# MainBoard_project.net
KiCad netlist of a schematic drawn in EAGLE
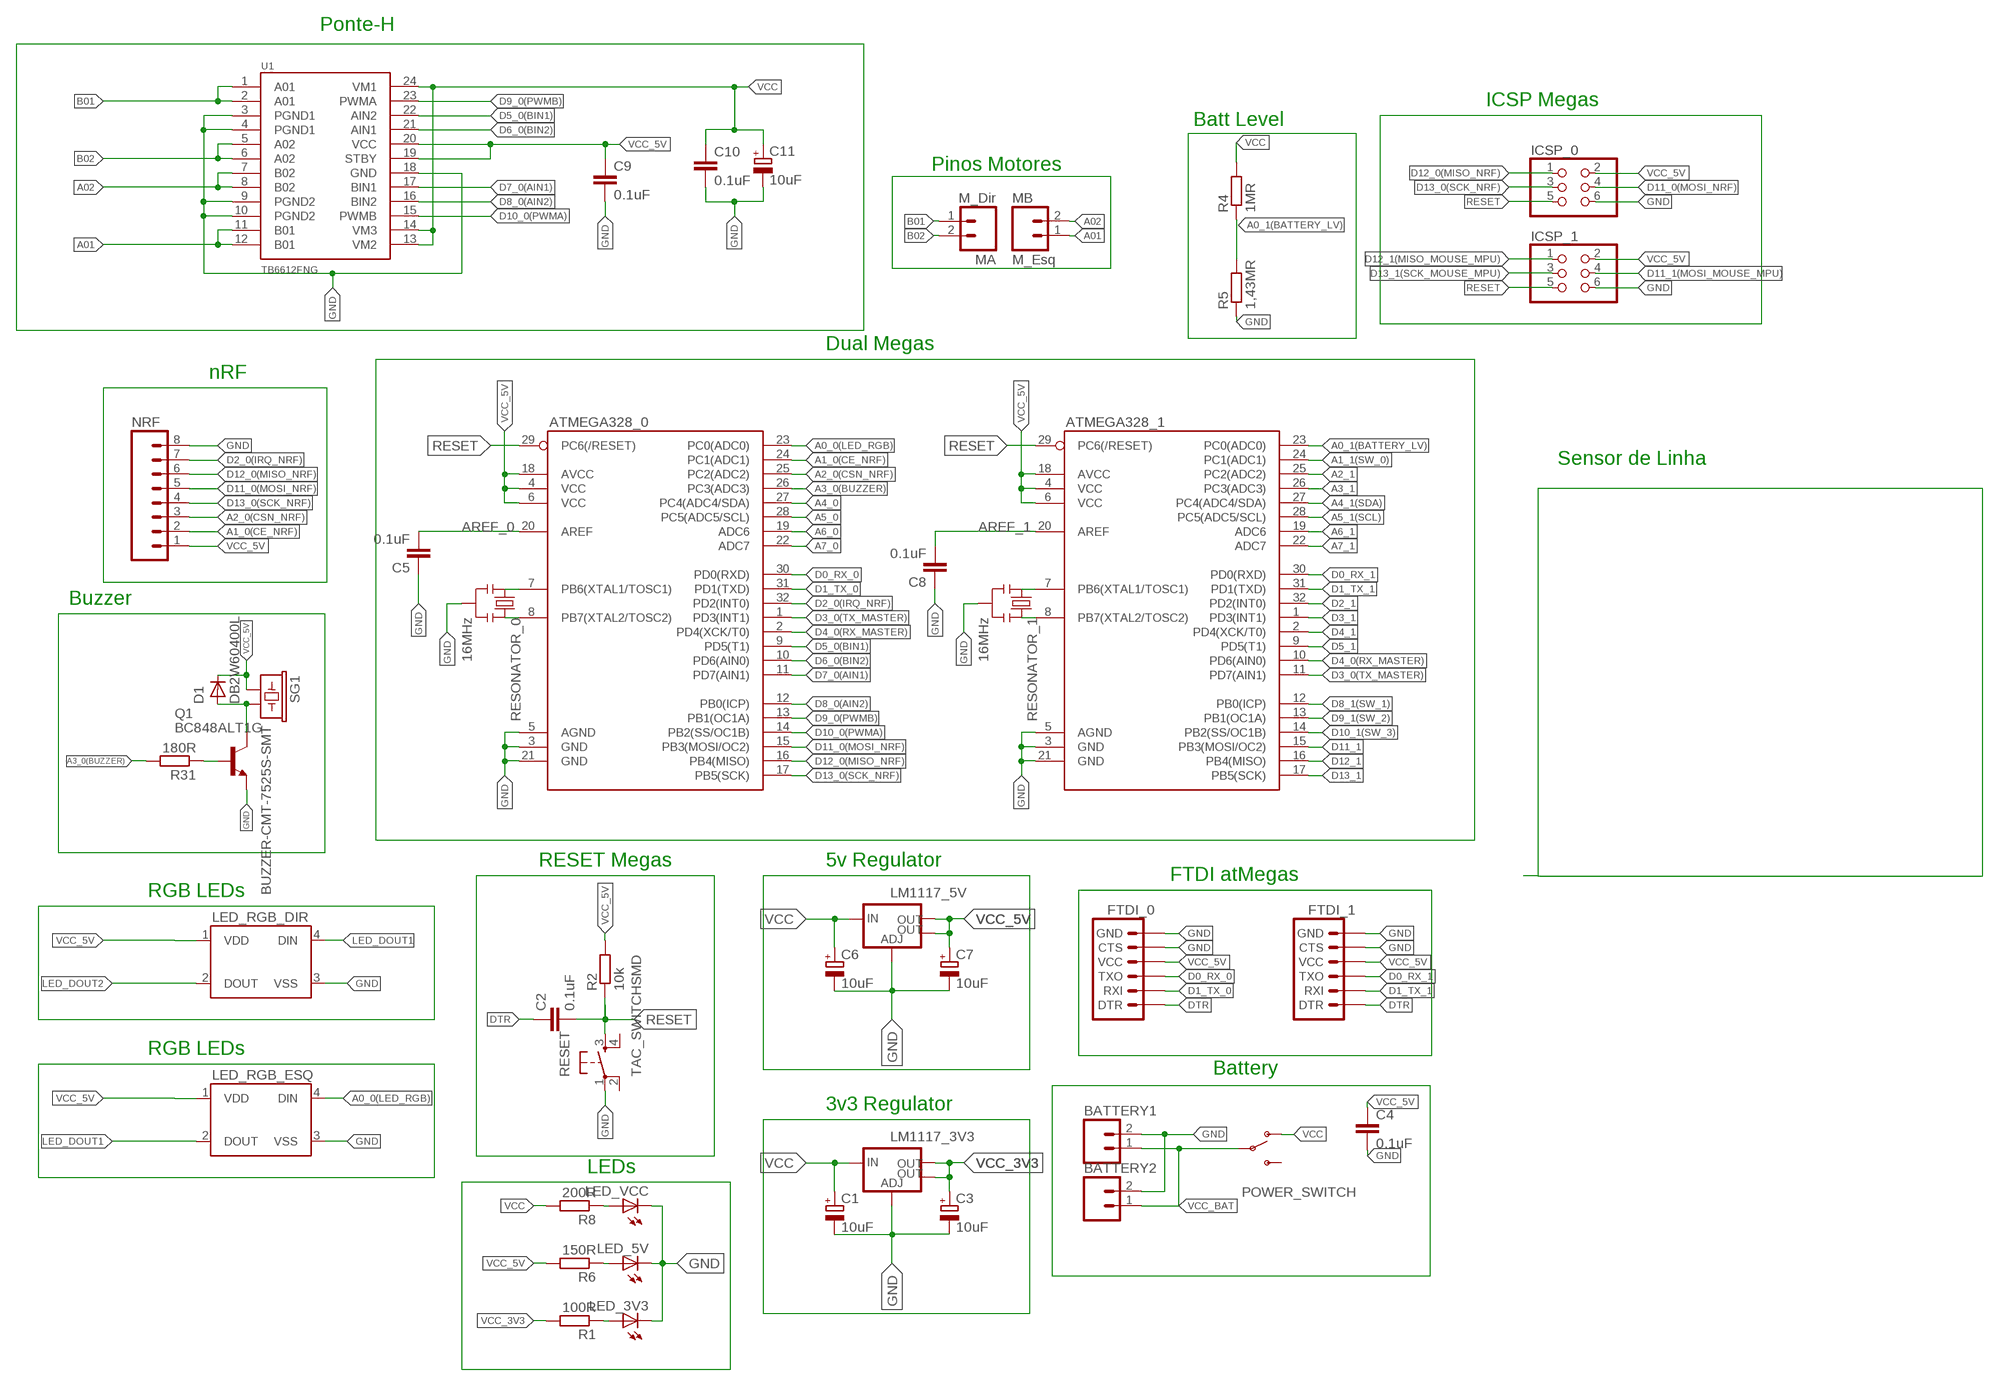
[diagram p0: schematic, sheet 1]

(export (version "E")
  (design (tool "Eeschema 10.0.6"))
  (components
    (comp (ref "ATMEGA328_0")
      (value "ATMEGA168")
      (footprint "eagle-import:TQFP32-08")
      (libsource (lib "eagle-import") (part "ATMEGA168"))
    )
    (comp (ref "ATMEGA328_1")
      (value "ATMEGA168")
      (footprint "eagle-import:TQFP32-08")
      (libsource (lib "eagle-import") (part "ATMEGA168"))
    )
    (comp (ref "BATTERY1")
      (value "M02POLAR")
      (footprint "eagle-import:MOLEX-1X2")
      (libsource (lib "eagle-import") (part "M02POLAR"))
    )
    (comp (ref "BATTERY2")
      (value "M02POLAR")
      (footprint "eagle-import:MOLEX-1X2")
      (libsource (lib "eagle-import") (part "M02POLAR"))
    )
    (comp (ref "C1")
      (value "10uF")
      (footprint "eagle-import:B_3528-21W")
      (libsource (lib "eagle-import") (part "CPOL-EUB/3528-21W"))
    )
    (comp (ref "C2")
      (value "0.1uF")
      (footprint "eagle-import:C0805K")
      (libsource (lib "eagle-import") (part "C-EUC0805K"))
    )
    (comp (ref "C3")
      (value "10uF")
      (footprint "eagle-import:B_3528-21W")
      (libsource (lib "eagle-import") (part "CPOL-EUB/3528-21W"))
    )
    (comp (ref "C4")
      (value "0.1uF")
      (footprint "eagle-import:C0805K")
      (libsource (lib "eagle-import") (part "C-EUC0805K"))
    )
    (comp (ref "C5")
      (value "0.1uF")
      (footprint "eagle-import:C0805K")
      (libsource (lib "eagle-import") (part "C-EUC0805K"))
    )
    (comp (ref "C6")
      (value "10uF")
      (footprint "eagle-import:B_3528-21W")
      (libsource (lib "eagle-import") (part "CPOL-EUB/3528-21W"))
    )
    (comp (ref "C7")
      (value "10uF")
      (footprint "eagle-import:B_3528-21W")
      (libsource (lib "eagle-import") (part "CPOL-EUB/3528-21W"))
    )
    (comp (ref "C8")
      (value "0.1uF")
      (footprint "eagle-import:C0805K")
      (libsource (lib "eagle-import") (part "C-EUC0805K"))
    )
    (comp (ref "C9")
      (value "0.1uF")
      (footprint "eagle-import:C0805K")
      (libsource (lib "eagle-import") (part "C-EUC0805K"))
    )
    (comp (ref "C10")
      (value "0.1uF")
      (footprint "eagle-import:C0805K")
      (libsource (lib "eagle-import") (part "C-EUC0805K"))
    )
    (comp (ref "C11")
      (value "10uF")
      (footprint "eagle-import:B_3528-21W")
      (libsource (lib "eagle-import") (part "CPOL-EUB/3528-21W"))
    )
    (comp (ref "D1")
      (value "DB2W60400L")
      (footprint "eagle-import:SMA-DO214AC")
      (libsource (lib "eagle-import") (part "GF1"))
    )
    (comp (ref "FTDI_0")
      (value "ARDUINO_SERIAL_PROGRAMPTH")
      (footprint "eagle-import:1X06")
      (libsource (lib "eagle-import") (part "ARDUINO_SERIAL_PROGRAMPTH"))
    )
    (comp (ref "FTDI_1")
      (value "ARDUINO_SERIAL_PROGRAMPTH")
      (footprint "eagle-import:1X06")
      (libsource (lib "eagle-import") (part "ARDUINO_SERIAL_PROGRAMPTH"))
    )
    (comp (ref "ICSP_0")
      (value "0114_PH254-203DF118A00V")
      (footprint "eagle-import:2X03")
      (fields (field (name "PART_NUMBER") "PH254-203DF118A00V"))
      (libsource (lib "eagle-import") (part "0114_PH254-203DF118A00V"))
    )
    (comp (ref "ICSP_1")
      (value "0114_PH254-203DF118A00V")
      (footprint "eagle-import:2X03")
      (fields (field (name "PART_NUMBER") "PH254-203DF118A00V"))
      (libsource (lib "eagle-import") (part "0114_PH254-203DF118A00V"))
    )
    (comp (ref "LED_3V3")
      (value "LEDCHIP-LED0805")
      (footprint "eagle-import:CHIP-LED0805")
      (libsource (lib "eagle-import") (part "LEDCHIP-LED0805"))
    )
    (comp (ref "LED_5V")
      (value "LEDCHIP-LED0805")
      (footprint "eagle-import:CHIP-LED0805")
      (libsource (lib "eagle-import") (part "LEDCHIP-LED0805"))
    )
    (comp (ref "LED_RGB_DIR")
      (value "WS2812B")
      (footprint "eagle-import:WS2812B")
      (libsource (lib "eagle-import") (part "WS2812B"))
    )
    (comp (ref "LED_RGB_ESQ")
      (value "WS2812B")
      (footprint "eagle-import:WS2812B")
      (libsource (lib "eagle-import") (part "WS2812B"))
    )
    (comp (ref "LED_VCC")
      (value "LEDCHIP-LED0805")
      (footprint "eagle-import:CHIP-LED0805")
      (libsource (lib "eagle-import") (part "LEDCHIP-LED0805"))
    )
    (comp (ref "LM1117_3V3")
      (value "V_REG_LM1117SOT223")
      (footprint "eagle-import:SOT223")
      (libsource (lib "eagle-import") (part "V_REG_LM1117SOT223"))
    )
    (comp (ref "LM1117_5V")
      (value "V_REG_LM1117SOT223")
      (footprint "eagle-import:SOT223")
      (libsource (lib "eagle-import") (part "V_REG_LM1117SOT223"))
    )
    (comp (ref "MA")
      (value "M_Dir")
      (footprint "eagle-import:MOLEX-1X2")
      (libsource (lib "eagle-import") (part "M02POLAR"))
    )
    (comp (ref "MB")
      (value "M_Esq")
      (footprint "eagle-import:MOLEX-1X2")
      (libsource (lib "eagle-import") (part "M02POLAR"))
    )
    (comp (ref "NRF")
      (value "M08")
      (footprint "eagle-import:1X08_ROUND")
      (libsource (lib "eagle-import") (part "M08"))
    )
    (comp (ref "POWER_SWITCH")
      (value "SWITCH-SPDTPTH")
      (footprint "eagle-import:SWITCH-SPDT")
      (libsource (lib "eagle-import") (part "SWITCH-SPDTPTH"))
    )
    (comp (ref "Q1")
      (value "BC848ALT1G")
      (footprint "eagle-import:SOT23")
      (libsource (lib "eagle-import") (part "BC848SMDALT1"))
    )
    (comp (ref "R1")
      (value "100R")
      (footprint "eagle-import:R0805")
      (libsource (lib "eagle-import") (part "R-EU_R0805"))
    )
    (comp (ref "R2")
      (value "10k")
      (footprint "eagle-import:R0805")
      (libsource (lib "eagle-import") (part "R-EU_R0805"))
    )
    (comp (ref "R4")
      (value "1MR")
      (footprint "eagle-import:R0805")
      (libsource (lib "eagle-import") (part "R-EU_R0805"))
    )
    (comp (ref "R5")
      (value "1,43MR")
      (footprint "eagle-import:R0805")
      (libsource (lib "eagle-import") (part "R-EU_R0805"))
    )
    (comp (ref "R6")
      (value "150R")
      (footprint "eagle-import:R0805")
      (libsource (lib "eagle-import") (part "R-EU_R0805"))
    )
    (comp (ref "R8")
      (value "200R")
      (footprint "eagle-import:R0805")
      (libsource (lib "eagle-import") (part "R-EU_R0805"))
    )
    (comp (ref "R31")
      (value "180R")
      (footprint "eagle-import:R0805")
      (libsource (lib "eagle-import") (part "R-EU_R0805"))
    )
    (comp (ref "RESET")
      (value "TAC_SWITCHSMD")
      (footprint "eagle-import:TACTILE-SWITCH-SMD")
      (libsource (lib "eagle-import") (part "TAC_SWITCHSMD"))
    )
    (comp (ref "RESONATOR_0")
      (value "16MHz")
      (footprint "eagle-import:RESONATOR-SMD")
      (libsource (lib "eagle-import") (part "RESONATOR16MHZ"))
    )
    (comp (ref "RESONATOR_1")
      (value "16MHz")
      (footprint "eagle-import:RESONATOR-SMD")
      (libsource (lib "eagle-import") (part "RESONATOR16MHZ"))
    )
    (comp (ref "SG1")
      (value "BUZZER-CMT-7525S-SMT")
      (footprint "eagle-import:CMT-7525S-SMT")
      (libsource (lib "eagle-import") (part "BUZZER-CMT-7525S-SMT"))
    )
    (comp (ref "U1")
      (value "TB6612FNG")
      (footprint "eagle-import:SSOP24")
      (libsource (lib "eagle-import") (part "TB6621FNG"))
    )
  )
  (nets
    (net (code "1") (name "/AREF_0") (class "Default")
      (node (ref "ATMEGA328_0") (pin "20") (pinfunction "AREF_20") (pintype "bidirectional"))
      (node (ref "C5") (pin "2") (pinfunction "2_2") (pintype "passive"))
    )
    (net (code "2") (name "/AREF_1") (class "Default")
      (node (ref "ATMEGA328_1") (pin "20") (pinfunction "AREF_20") (pintype "bidirectional"))
      (node (ref "C8") (pin "2") (pinfunction "2_2") (pintype "passive"))
    )
    (net (code "3") (name "A0_0(LED_RGB)") (class "Default")
      (node (ref "ATMEGA328_0") (pin "23") (pinfunction "PC0(ADC0)_23") (pintype "bidirectional"))
      (node (ref "LED_RGB_ESQ") (pin "4") (pinfunction "DIN_4") (pintype "input"))
    )
    (net (code "4") (name "A0_1(BATTERY_LV)") (class "Default")
      (node (ref "ATMEGA328_1") (pin "23") (pinfunction "PC0(ADC0)_23") (pintype "bidirectional"))
      (node (ref "R4") (pin "1") (pinfunction "1_1") (pintype "passive"))
      (node (ref "R5") (pin "2") (pinfunction "2_2") (pintype "passive"))
    )
    (net (code "5") (name "A01") (class "Default")
      (node (ref "MB") (pin "1") (pinfunction "1_1") (pintype "passive"))
      (node (ref "U1") (pin "11") (pinfunction "B01_11") (pintype "bidirectional"))
      (node (ref "U1") (pin "12") (pinfunction "B01_12") (pintype "bidirectional"))
    )
    (net (code "6") (name "A1_0(CE_NRF)") (class "Default")
      (node (ref "ATMEGA328_0") (pin "24") (pinfunction "PC1(ADC1)_24") (pintype "bidirectional"))
      (node (ref "NRF") (pin "2") (pinfunction "2_2") (pintype "passive"))
    )
    (net (code "7") (name "A1_1(SW_0)") (class "Default")
      (node (ref "ATMEGA328_1") (pin "24") (pinfunction "PC1(ADC1)_24") (pintype "bidirectional"))
    )
    (net (code "8") (name "A02") (class "Default")
      (node (ref "MB") (pin "2") (pinfunction "2_2") (pintype "passive"))
      (node (ref "U1") (pin "7") (pinfunction "B02_7") (pintype "bidirectional"))
      (node (ref "U1") (pin "8") (pinfunction "B02_8") (pintype "bidirectional"))
    )
    (net (code "9") (name "A2_0(CSN_NRF)") (class "Default")
      (node (ref "ATMEGA328_0") (pin "25") (pinfunction "PC2(ADC2)_25") (pintype "bidirectional"))
      (node (ref "NRF") (pin "3") (pinfunction "3_3") (pintype "passive"))
    )
    (net (code "10") (name "A2_1") (class "Default")
      (node (ref "ATMEGA328_1") (pin "25") (pinfunction "PC2(ADC2)_25") (pintype "bidirectional"))
    )
    (net (code "11") (name "A3_0(BUZZER)") (class "Default")
      (node (ref "ATMEGA328_0") (pin "26") (pinfunction "PC3(ADC3)_26") (pintype "bidirectional"))
      (node (ref "R31") (pin "2") (pinfunction "2_2") (pintype "passive"))
    )
    (net (code "12") (name "A3_1") (class "Default")
      (node (ref "ATMEGA328_1") (pin "26") (pinfunction "PC3(ADC3)_26") (pintype "bidirectional"))
    )
    (net (code "13") (name "A4_0") (class "Default")
      (node (ref "ATMEGA328_0") (pin "27") (pinfunction "PC4(ADC4/SDA)_27") (pintype "bidirectional"))
    )
    (net (code "14") (name "A4_1(SDA)") (class "Default")
      (node (ref "ATMEGA328_1") (pin "27") (pinfunction "PC4(ADC4/SDA)_27") (pintype "bidirectional"))
    )
    (net (code "15") (name "A5_0") (class "Default")
      (node (ref "ATMEGA328_0") (pin "28") (pinfunction "PC5(ADC5/SCL)_28") (pintype "bidirectional"))
    )
    (net (code "16") (name "A5_1(SCL)") (class "Default")
      (node (ref "ATMEGA328_1") (pin "28") (pinfunction "PC5(ADC5/SCL)_28") (pintype "bidirectional"))
    )
    (net (code "17") (name "A6_0") (class "Default")
      (node (ref "ATMEGA328_0") (pin "19") (pinfunction "ADC6_19") (pintype "bidirectional"))
    )
    (net (code "18") (name "A6_1") (class "Default")
      (node (ref "ATMEGA328_1") (pin "19") (pinfunction "ADC6_19") (pintype "bidirectional"))
    )
    (net (code "19") (name "A7_0") (class "Default")
      (node (ref "ATMEGA328_0") (pin "22") (pinfunction "ADC7_22") (pintype "bidirectional"))
    )
    (net (code "20") (name "A7_1") (class "Default")
      (node (ref "ATMEGA328_1") (pin "22") (pinfunction "ADC7_22") (pintype "bidirectional"))
    )
    (net (code "21") (name "B01") (class "Default")
      (node (ref "MA") (pin "1") (pinfunction "1_1") (pintype "passive"))
      (node (ref "U1") (pin "1") (pinfunction "A01_1") (pintype "bidirectional"))
      (node (ref "U1") (pin "2") (pinfunction "A01_2") (pintype "bidirectional"))
    )
    (net (code "22") (name "B02") (class "Default")
      (node (ref "MA") (pin "2") (pinfunction "2_2") (pintype "passive"))
      (node (ref "U1") (pin "5") (pinfunction "A02_5") (pintype "bidirectional"))
      (node (ref "U1") (pin "6") (pinfunction "A02_6") (pintype "bidirectional"))
    )
    (net (code "23") (name "D0_RX_0") (class "Default")
      (node (ref "ATMEGA328_0") (pin "30") (pinfunction "PD0(RXD)_30") (pintype "bidirectional"))
      (node (ref "FTDI_0") (pin "3") (pinfunction "TXO_3") (pintype "passive"))
    )
    (net (code "24") (name "D0_RX_1") (class "Default")
      (node (ref "ATMEGA328_1") (pin "30") (pinfunction "PD0(RXD)_30") (pintype "bidirectional"))
      (node (ref "FTDI_1") (pin "3") (pinfunction "TXO_3") (pintype "passive"))
    )
    (net (code "25") (name "D1_TX_0") (class "Default")
      (node (ref "ATMEGA328_0") (pin "31") (pinfunction "PD1(TXD)_31") (pintype "bidirectional"))
      (node (ref "FTDI_0") (pin "2") (pinfunction "RXI_2") (pintype "passive"))
    )
    (net (code "26") (name "D1_TX_1") (class "Default")
      (node (ref "ATMEGA328_1") (pin "31") (pinfunction "PD1(TXD)_31") (pintype "bidirectional"))
      (node (ref "FTDI_1") (pin "2") (pinfunction "RXI_2") (pintype "passive"))
    )
    (net (code "27") (name "D2_0(IRQ_NRF)") (class "Default")
      (node (ref "ATMEGA328_0") (pin "32") (pinfunction "PD2(INT0)_32") (pintype "bidirectional"))
      (node (ref "NRF") (pin "7") (pinfunction "7_7") (pintype "passive"))
    )
    (net (code "28") (name "D2_1") (class "Default")
      (node (ref "ATMEGA328_1") (pin "32") (pinfunction "PD2(INT0)_32") (pintype "bidirectional"))
    )
    (net (code "29") (name "D3_0(TX_MASTER)") (class "Default")
      (node (ref "ATMEGA328_0") (pin "1") (pinfunction "PD3(INT1)_1") (pintype "bidirectional"))
      (node (ref "ATMEGA328_1") (pin "11") (pinfunction "PD7(AIN1)_11") (pintype "bidirectional"))
    )
    (net (code "30") (name "D3_1") (class "Default")
      (node (ref "ATMEGA328_1") (pin "1") (pinfunction "PD3(INT1)_1") (pintype "bidirectional"))
    )
    (net (code "31") (name "D4_0(RX_MASTER)") (class "Default")
      (node (ref "ATMEGA328_0") (pin "2") (pinfunction "PD4(XCK/T0)_2") (pintype "bidirectional"))
      (node (ref "ATMEGA328_1") (pin "10") (pinfunction "PD6(AIN0)_10") (pintype "bidirectional"))
    )
    (net (code "32") (name "D4_1") (class "Default")
      (node (ref "ATMEGA328_1") (pin "2") (pinfunction "PD4(XCK/T0)_2") (pintype "bidirectional"))
    )
    (net (code "33") (name "D5_0(BIN1)") (class "Default")
      (node (ref "ATMEGA328_0") (pin "9") (pinfunction "PD5(T1)_9") (pintype "bidirectional"))
      (node (ref "U1") (pin "22") (pinfunction "AIN2_22") (pintype "bidirectional"))
    )
    (net (code "34") (name "D5_1") (class "Default")
      (node (ref "ATMEGA328_1") (pin "9") (pinfunction "PD5(T1)_9") (pintype "bidirectional"))
    )
    (net (code "35") (name "D6_0(BIN2)") (class "Default")
      (node (ref "ATMEGA328_0") (pin "10") (pinfunction "PD6(AIN0)_10") (pintype "bidirectional"))
      (node (ref "U1") (pin "21") (pinfunction "AIN1_21") (pintype "bidirectional"))
    )
    (net (code "36") (name "D7_0(AIN1)") (class "Default")
      (node (ref "ATMEGA328_0") (pin "11") (pinfunction "PD7(AIN1)_11") (pintype "bidirectional"))
      (node (ref "U1") (pin "17") (pinfunction "BIN1_17") (pintype "bidirectional"))
    )
    (net (code "37") (name "D8_0(AIN2)") (class "Default")
      (node (ref "ATMEGA328_0") (pin "12") (pinfunction "PB0(ICP)_12") (pintype "bidirectional"))
      (node (ref "U1") (pin "16") (pinfunction "BIN2_16") (pintype "bidirectional"))
    )
    (net (code "38") (name "D8_1(SW_1)") (class "Default")
      (node (ref "ATMEGA328_1") (pin "12") (pinfunction "PB0(ICP)_12") (pintype "bidirectional"))
    )
    (net (code "39") (name "D9_0(PWMB)") (class "Default")
      (node (ref "ATMEGA328_0") (pin "13") (pinfunction "PB1(OC1A)_13") (pintype "bidirectional"))
      (node (ref "U1") (pin "23") (pinfunction "PWMA_23") (pintype "bidirectional"))
    )
    (net (code "40") (name "D9_1(SW_2)") (class "Default")
      (node (ref "ATMEGA328_1") (pin "13") (pinfunction "PB1(OC1A)_13") (pintype "bidirectional"))
    )
    (net (code "41") (name "D10_0(PWMA)") (class "Default")
      (node (ref "ATMEGA328_0") (pin "14") (pinfunction "PB2(SS/OC1B)_14") (pintype "bidirectional"))
      (node (ref "U1") (pin "15") (pinfunction "PWMB_15") (pintype "bidirectional"))
    )
    (net (code "42") (name "D10_1(SW_3)") (class "Default")
      (node (ref "ATMEGA328_1") (pin "14") (pinfunction "PB2(SS/OC1B)_14") (pintype "bidirectional"))
    )
    (net (code "43") (name "D11_0(MOSI_NRF)") (class "Default")
      (node (ref "ATMEGA328_0") (pin "15") (pinfunction "PB3(MOSI/OC2)_15") (pintype "bidirectional"))
      (node (ref "ICSP_0") (pin "4") (pinfunction "4_4") (pintype "passive"))
      (node (ref "NRF") (pin "5") (pinfunction "5_5") (pintype "passive"))
    )
    (net (code "44") (name "D11_1") (class "Default")
      (node (ref "ATMEGA328_1") (pin "15") (pinfunction "PB3(MOSI/OC2)_15") (pintype "bidirectional"))
    )
    (net (code "45") (name "D11_1(MOSI_MOUSE_MPU)") (class "Default")
      (node (ref "ICSP_1") (pin "4") (pinfunction "4_4") (pintype "passive"))
    )
    (net (code "46") (name "D12_0(MISO_NRF)") (class "Default")
      (node (ref "ATMEGA328_0") (pin "16") (pinfunction "PB4(MISO)_16") (pintype "bidirectional"))
      (node (ref "ICSP_0") (pin "1") (pinfunction "1_1") (pintype "passive"))
      (node (ref "NRF") (pin "6") (pinfunction "6_6") (pintype "passive"))
    )
    (net (code "47") (name "D12_1") (class "Default")
      (node (ref "ATMEGA328_1") (pin "16") (pinfunction "PB4(MISO)_16") (pintype "bidirectional"))
    )
    (net (code "48") (name "D12_1(MISO_MOUSE_MPU)") (class "Default")
      (node (ref "ICSP_1") (pin "1") (pinfunction "1_1") (pintype "passive"))
    )
    (net (code "49") (name "D13_0(SCK_NRF)") (class "Default")
      (node (ref "ATMEGA328_0") (pin "17") (pinfunction "PB5(SCK)_17") (pintype "bidirectional"))
      (node (ref "ICSP_0") (pin "3") (pinfunction "3_3") (pintype "passive"))
      (node (ref "NRF") (pin "4") (pinfunction "4_4") (pintype "passive"))
    )
    (net (code "50") (name "D13_1") (class "Default")
      (node (ref "ATMEGA328_1") (pin "17") (pinfunction "PB5(SCK)_17") (pintype "bidirectional"))
    )
    (net (code "51") (name "D13_1(SCK_MOUSE_MPU)") (class "Default")
      (node (ref "ICSP_1") (pin "3") (pinfunction "3_3") (pintype "passive"))
    )
    (net (code "52") (name "DTR") (class "Default")
      (node (ref "C2") (pin "1") (pinfunction "1_1") (pintype "passive"))
      (node (ref "FTDI_0") (pin "1") (pinfunction "DTR_1") (pintype "passive"))
      (node (ref "FTDI_1") (pin "1") (pinfunction "DTR_1") (pintype "passive"))
    )
    (net (code "53") (name "GND") (class "Default")
      (node (ref "ATMEGA328_0") (pin "21") (pinfunction "GND_21") (pintype "bidirectional"))
      (node (ref "ATMEGA328_0") (pin "3") (pinfunction "GND_3") (pintype "bidirectional"))
      (node (ref "ATMEGA328_0") (pin "5") (pinfunction "AGND_5") (pintype "bidirectional"))
      (node (ref "ATMEGA328_1") (pin "21") (pinfunction "GND_21") (pintype "bidirectional"))
      (node (ref "ATMEGA328_1") (pin "3") (pinfunction "GND_3") (pintype "bidirectional"))
      (node (ref "ATMEGA328_1") (pin "5") (pinfunction "AGND_5") (pintype "bidirectional"))
      (node (ref "BATTERY1") (pin "2") (pinfunction "2_2") (pintype "passive"))
      (node (ref "BATTERY2") (pin "2") (pinfunction "2_2") (pintype "passive"))
      (node (ref "C1") (pin "-") (pinfunction "-_-") (pintype "passive"))
      (node (ref "C10") (pin "2") (pinfunction "2_2") (pintype "passive"))
      (node (ref "C11") (pin "-") (pinfunction "-_-") (pintype "passive"))
      (node (ref "C3") (pin "-") (pinfunction "-_-") (pintype "passive"))
      (node (ref "C4") (pin "2") (pinfunction "2_2") (pintype "passive"))
      (node (ref "C5") (pin "1") (pinfunction "1_1") (pintype "passive"))
      (node (ref "C6") (pin "-") (pinfunction "-_-") (pintype "passive"))
      (node (ref "C7") (pin "-") (pinfunction "-_-") (pintype "passive"))
      (node (ref "C8") (pin "1") (pinfunction "1_1") (pintype "passive"))
      (node (ref "C9") (pin "2") (pinfunction "2_2") (pintype "passive"))
      (node (ref "FTDI_0") (pin "5") (pinfunction "CTS_5") (pintype "passive"))
      (node (ref "FTDI_0") (pin "6") (pinfunction "GND_6") (pintype "passive"))
      (node (ref "FTDI_1") (pin "5") (pinfunction "CTS_5") (pintype "passive"))
      (node (ref "FTDI_1") (pin "6") (pinfunction "GND_6") (pintype "passive"))
      (node (ref "ICSP_0") (pin "6") (pinfunction "6_6") (pintype "passive"))
      (node (ref "ICSP_1") (pin "6") (pinfunction "6_6") (pintype "passive"))
      (node (ref "LED_3V3") (pin "C") (pinfunction "C_C") (pintype "passive"))
      (node (ref "LED_5V") (pin "C") (pinfunction "C_C") (pintype "passive"))
      (node (ref "LED_RGB_DIR") (pin "3") (pinfunction "VSS_3") (pintype "power_in"))
      (node (ref "LED_RGB_ESQ") (pin "3") (pinfunction "VSS_3") (pintype "power_in"))
      (node (ref "LED_VCC") (pin "C") (pinfunction "C_C") (pintype "passive"))
      (node (ref "LM1117_3V3") (pin "1") (pinfunction "ADJ_1") (pintype "input"))
      (node (ref "LM1117_5V") (pin "1") (pinfunction "ADJ_1") (pintype "input"))
      (node (ref "NRF") (pin "8") (pinfunction "8_8") (pintype "passive"))
      (node (ref "Q1") (pin "2") (pinfunction "E_2") (pintype "passive"))
      (node (ref "R5") (pin "1") (pinfunction "1_1") (pintype "passive"))
      (node (ref "RESET") (pin "1") (pinfunction "1_1") (pintype "passive"))
      (node (ref "RESONATOR_0") (pin "2") (pinfunction "2_2") (pintype "passive"))
      (node (ref "RESONATOR_1") (pin "2") (pinfunction "2_2") (pintype "passive"))
      (node (ref "U1") (pin "10") (pinfunction "PGND2_10") (pintype "bidirectional"))
      (node (ref "U1") (pin "18") (pinfunction "GND_18") (pintype "bidirectional"))
      (node (ref "U1") (pin "3") (pinfunction "PGND1_3") (pintype "bidirectional"))
      (node (ref "U1") (pin "4") (pinfunction "PGND1_4") (pintype "bidirectional"))
      (node (ref "U1") (pin "9") (pinfunction "PGND2_9") (pintype "bidirectional"))
    )
    (net (code "54") (name "LED_DOUT1") (class "Default")
      (node (ref "LED_RGB_DIR") (pin "4") (pinfunction "DIN_4") (pintype "input"))
      (node (ref "LED_RGB_ESQ") (pin "2") (pinfunction "DOUT_2") (pintype "output"))
    )
    (net (code "55") (name "LED_DOUT2") (class "Default")
      (node (ref "LED_RGB_DIR") (pin "2") (pinfunction "DOUT_2") (pintype "output"))
    )
    (net (code "56") (name "Net-(ATMEGA328_0-PB6(XTAL1{slash}TOSC1))") (class "Default")
      (node (ref "ATMEGA328_0") (pin "7") (pinfunction "PB6(XTAL1/TOSC1)_7") (pintype "bidirectional"))
      (node (ref "RESONATOR_0") (pin "1") (pinfunction "1_1") (pintype "passive"))
    )
    (net (code "57") (name "Net-(ATMEGA328_0-PB7(XTAL2{slash}TOSC2))") (class "Default")
      (node (ref "ATMEGA328_0") (pin "8") (pinfunction "PB7(XTAL2/TOSC2)_8") (pintype "bidirectional"))
      (node (ref "RESONATOR_0") (pin "3") (pinfunction "3_3") (pintype "passive"))
    )
    (net (code "58") (name "Net-(ATMEGA328_1-PB6(XTAL1{slash}TOSC1))") (class "Default")
      (node (ref "ATMEGA328_1") (pin "7") (pinfunction "PB6(XTAL1/TOSC1)_7") (pintype "bidirectional"))
      (node (ref "RESONATOR_1") (pin "1") (pinfunction "1_1") (pintype "passive"))
    )
    (net (code "59") (name "Net-(ATMEGA328_1-PB7(XTAL2{slash}TOSC2))") (class "Default")
      (node (ref "ATMEGA328_1") (pin "8") (pinfunction "PB7(XTAL2/TOSC2)_8") (pintype "bidirectional"))
      (node (ref "RESONATOR_1") (pin "3") (pinfunction "3_3") (pintype "passive"))
    )
    (net (code "60") (name "Net-(LED_3V3-PadA)") (class "Default")
      (node (ref "LED_3V3") (pin "A") (pinfunction "A_A") (pintype "passive"))
      (node (ref "R1") (pin "1") (pinfunction "1_1") (pintype "passive"))
    )
    (net (code "61") (name "Net-(LED_5V-PadA)") (class "Default")
      (node (ref "LED_5V") (pin "A") (pinfunction "A_A") (pintype "passive"))
      (node (ref "R6") (pin "1") (pinfunction "1_1") (pintype "passive"))
    )
    (net (code "62") (name "Net-(LED_VCC-PadA)") (class "Default")
      (node (ref "LED_VCC") (pin "A") (pinfunction "A_A") (pintype "passive"))
      (node (ref "R8") (pin "1") (pinfunction "1_1") (pintype "passive"))
    )
    (net (code "63") (name "Net-(Q1-B)") (class "Default")
      (node (ref "Q1") (pin "1") (pinfunction "B_1") (pintype "passive"))
      (node (ref "R31") (pin "1") (pinfunction "1_1") (pintype "passive"))
    )
    (net (code "64") (name "Net-(Q1-C)") (class "Default")
      (node (ref "D1") (pin "A") (pinfunction "A_A") (pintype "passive"))
      (node (ref "Q1") (pin "3") (pinfunction "C_3") (pintype "passive"))
      (node (ref "SG1") (pin "P$1") (pinfunction "2_P$1") (pintype "passive"))
      (node (ref "SG1") (pin "P$2") (pinfunction "2_P$2") (pintype "passive"))
    )
    (net (code "65") (name "RESET") (class "Default")
      (node (ref "ATMEGA328_0") (pin "29") (pinfunction "PC6(/RESET)_29") (pintype "bidirectional"))
      (node (ref "ATMEGA328_1") (pin "29") (pinfunction "PC6(/RESET)_29") (pintype "bidirectional"))
      (node (ref "C2") (pin "2") (pinfunction "2_2") (pintype "passive"))
      (node (ref "ICSP_0") (pin "5") (pinfunction "5_5") (pintype "passive"))
      (node (ref "ICSP_1") (pin "5") (pinfunction "5_5") (pintype "passive"))
      (node (ref "R2") (pin "1") (pinfunction "1_1") (pintype "passive"))
      (node (ref "RESET") (pin "3") (pinfunction "3_3") (pintype "passive"))
    )
    (net (code "66") (name "VCC") (class "Default")
      (node (ref "C1") (pin "+") (pinfunction "+_+") (pintype "passive"))
      (node (ref "C10") (pin "1") (pinfunction "1_1") (pintype "passive"))
      (node (ref "C11") (pin "+") (pinfunction "+_+") (pintype "passive"))
      (node (ref "C6") (pin "+") (pinfunction "+_+") (pintype "passive"))
      (node (ref "LM1117_3V3") (pin "3") (pinfunction "IN_3") (pintype "input"))
      (node (ref "LM1117_5V") (pin "3") (pinfunction "IN_3") (pintype "input"))
      (node (ref "POWER_SWITCH") (pin "1") (pinfunction "O_1") (pintype "passive"))
      (node (ref "R4") (pin "2") (pinfunction "2_2") (pintype "passive"))
      (node (ref "R8") (pin "2") (pinfunction "2_2") (pintype "passive"))
      (node (ref "U1") (pin "13") (pinfunction "VM2_13") (pintype "bidirectional"))
      (node (ref "U1") (pin "14") (pinfunction "VM3_14") (pintype "bidirectional"))
      (node (ref "U1") (pin "24") (pinfunction "VM1_24") (pintype "bidirectional"))
    )
    (net (code "67") (name "VCC_3V3") (class "Default")
      (node (ref "C3") (pin "+") (pinfunction "+_+") (pintype "passive"))
      (node (ref "LM1117_3V3") (pin "2") (pinfunction "OUT_2") (pintype "output"))
      (node (ref "LM1117_3V3") (pin "4") (pinfunction "OUT_4") (pintype "output"))
      (node (ref "R1") (pin "2") (pinfunction "2_2") (pintype "passive"))
    )
    (net (code "68") (name "VCC_5V") (class "Default")
      (node (ref "ATMEGA328_0") (pin "18") (pinfunction "AVCC_18") (pintype "bidirectional"))
      (node (ref "ATMEGA328_0") (pin "4") (pinfunction "VCC_4") (pintype "bidirectional"))
      (node (ref "ATMEGA328_0") (pin "6") (pinfunction "VCC_6") (pintype "bidirectional"))
      (node (ref "ATMEGA328_1") (pin "18") (pinfunction "AVCC_18") (pintype "bidirectional"))
      (node (ref "ATMEGA328_1") (pin "4") (pinfunction "VCC_4") (pintype "bidirectional"))
      (node (ref "ATMEGA328_1") (pin "6") (pinfunction "VCC_6") (pintype "bidirectional"))
      (node (ref "C4") (pin "1") (pinfunction "1_1") (pintype "passive"))
      (node (ref "C7") (pin "+") (pinfunction "+_+") (pintype "passive"))
      (node (ref "C9") (pin "1") (pinfunction "1_1") (pintype "passive"))
      (node (ref "D1") (pin "K") (pinfunction "C_K") (pintype "passive"))
      (node (ref "FTDI_0") (pin "4") (pinfunction "VCC_4") (pintype "passive"))
      (node (ref "FTDI_1") (pin "4") (pinfunction "VCC_4") (pintype "passive"))
      (node (ref "ICSP_0") (pin "2") (pinfunction "2_2") (pintype "passive"))
      (node (ref "ICSP_1") (pin "2") (pinfunction "2_2") (pintype "passive"))
      (node (ref "LED_RGB_DIR") (pin "1") (pinfunction "VDD_1") (pintype "power_in"))
      (node (ref "LED_RGB_ESQ") (pin "1") (pinfunction "VDD_1") (pintype "power_in"))
      (node (ref "LM1117_5V") (pin "2") (pinfunction "OUT_2") (pintype "output"))
      (node (ref "LM1117_5V") (pin "4") (pinfunction "OUT_4") (pintype "output"))
      (node (ref "NRF") (pin "1") (pinfunction "1_1") (pintype "passive"))
      (node (ref "R2") (pin "2") (pinfunction "2_2") (pintype "passive"))
      (node (ref "R6") (pin "2") (pinfunction "2_2") (pintype "passive"))
      (node (ref "SG1") (pin "P$3") (pinfunction "1_P$3") (pintype "passive"))
      (node (ref "SG1") (pin "P$4") (pinfunction "1_P$4") (pintype "passive"))
      (node (ref "U1") (pin "19") (pinfunction "STBY_19") (pintype "bidirectional"))
      (node (ref "U1") (pin "20") (pinfunction "VCC_20") (pintype "bidirectional"))
    )
    (net (code "69") (name "VCC_BAT") (class "Default")
      (node (ref "BATTERY1") (pin "1") (pinfunction "1_1") (pintype "passive"))
      (node (ref "BATTERY2") (pin "1") (pinfunction "1_1") (pintype "passive"))
      (node (ref "POWER_SWITCH") (pin "2") (pinfunction "P_2") (pintype "passive"))
    )
    (net (code "70") (name "unconnected-(POWER_SWITCH-S-Pad3)") (class "Default")
      (node (ref "POWER_SWITCH") (pin "3") (pinfunction "S_3") (pintype "passive"))
    )
    (net (code "71") (name "unconnected-(RESET-Pad2)") (class "Default")
      (node (ref "RESET") (pin "2") (pinfunction "2_2") (pintype "passive"))
    )
    (net (code "72") (name "unconnected-(RESET-Pad4)") (class "Default")
      (node (ref "RESET") (pin "4") (pinfunction "4_4") (pintype "passive"))
    )
  )
)
